# Sensors_Mic.net
KiCad netlist of a schematic drawn in Altium Designer
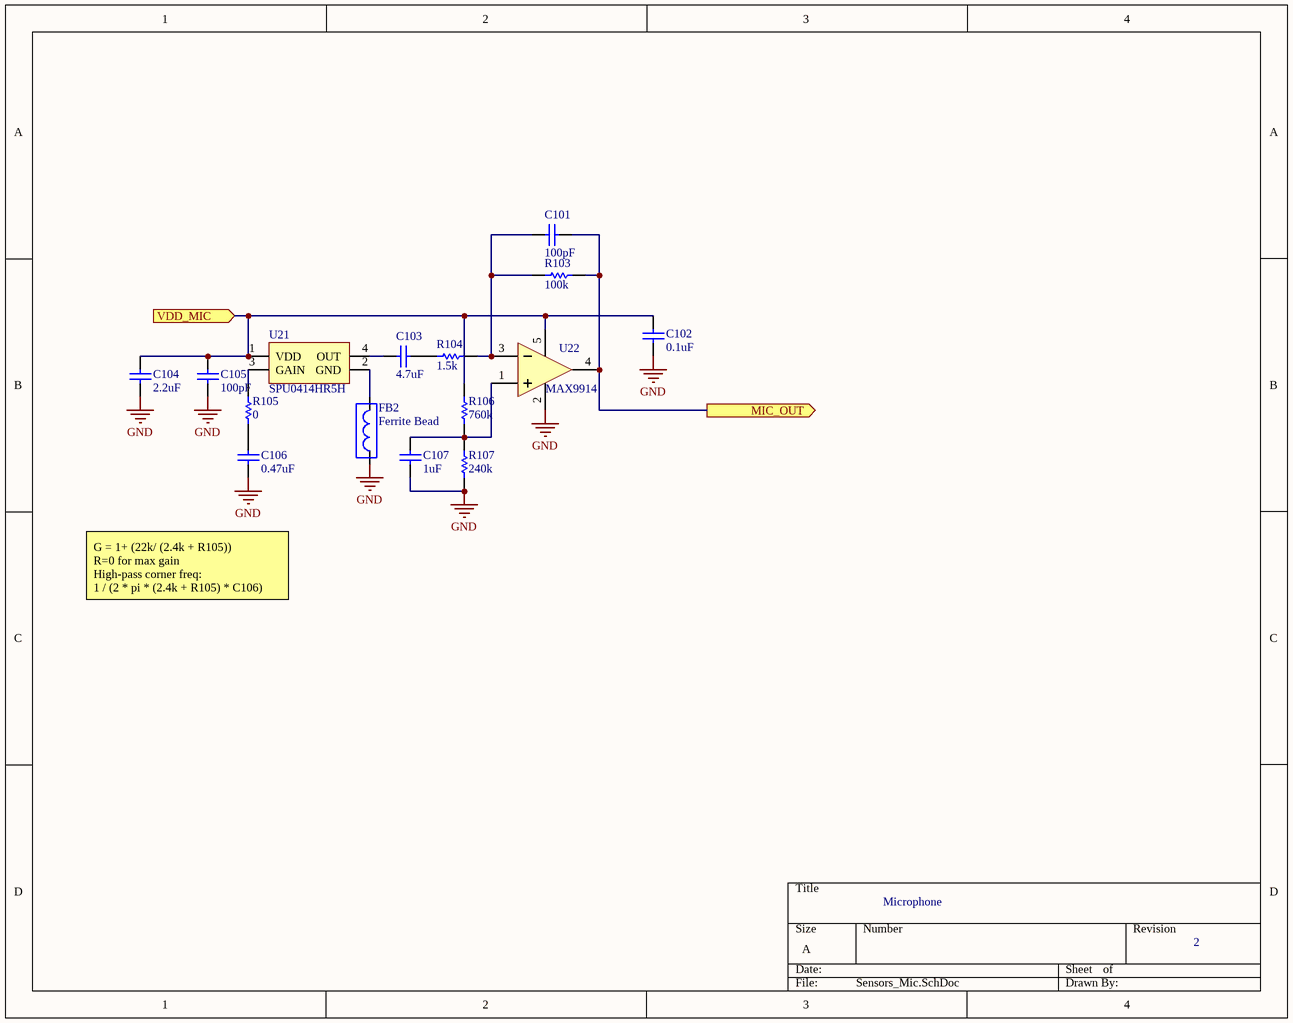
[diagram p0: Sensors_Mic.SchDoc]

(export (version "E")
  (design (tool "Eeschema 10.0.6"))
  (components
    (comp (ref "C101")
      (value "100pF")
      (footprint "0603")
      (description "Ceramic Capacitor (Surface Mount)")
      (fields
        (field (name "MANUFACTURER") "Kemet")
        (field (name "MANUFACTURER PART NUMBER") "C0603C101J5GACTU")
      )
      (libsource (lib "DRP_Basic_2014") (part "Cap"))
    )
    (comp (ref "C102")
      (value "0.1uF")
      (footprint "0603")
      (description "Ceramic Capacitor (Surface Mount)")
      (fields
        (field (name "MANUFACTURER") "Murata Electronics North America")
        (field (name "MANUFACTURER PART NUMBER") "GRM188R71C104KA01D")
      )
      (libsource (lib "DRP_Basic_2014") (part "Cap"))
    )
    (comp (ref "C103")
      (value "4.7uF")
      (footprint "0603")
      (description "Ceramic Capacitor (Surface Mount)")
      (fields
        (field (name "MANUFACTURER") "Samsung Electro-Mechanics")
        (field (name "MANUFACTURER PART NUMBER") "CL10B475KQ8NQNC")
      )
      (libsource (lib "DRP_Basic_2014") (part "Cap"))
    )
    (comp (ref "C104")
      (value "2.2uF")
      (footprint "0603")
      (description "Ceramic Capacitor (Surface Mount)")
      (fields
        (field (name "MANUFACTURER") "Murata Electronics North America")
        (field (name "MANUFACTURER PART NUMBER") "GRM188R61C225KE15D")
      )
      (libsource (lib "DRP_Basic_2014") (part "Cap"))
    )
    (comp (ref "C105")
      (value "100pF")
      (footprint "0603")
      (description "Ceramic Capacitor (Surface Mount)")
      (fields
        (field (name "MANUFACTURER") "Kemet")
        (field (name "MANUFACTURER PART NUMBER") "C0603C101J5GACTU")
      )
      (libsource (lib "DRP_Basic_2014") (part "Cap"))
    )
    (comp (ref "C106")
      (value "0.47uF")
      (footprint "0603")
      (description "Ceramic Capacitor (Surface Mount)")
      (fields
        (field (name "MANUFACTURER") "TDK Corporation")
        (field (name "MANUFACTURER PART NUMBER") "C1608X7R1C474K080AC")
      )
      (libsource (lib "DRP_Basic_2014") (part "Cap"))
    )
    (comp (ref "C107")
      (value "1uF")
      (footprint "0603")
      (description "Ceramic Capacitor (Surface Mount)")
      (fields
        (field (name "MANUFACTURER") "Murata Electronics North America")
        (field (name "MANUFACTURER PART NUMBER") "GRM188R61A105KA61D")
      )
      (libsource (lib "DRP_Basic_2014") (part "Cap"))
    )
    (comp (ref "FB2")
      (value "Ferrite Bead")
      (footprint "0603")
      (description "Ferrite bead, RF choke")
      (fields
        (field (name "DIGI-KEY PART NUMBER") "490-5216-1-ND")
        (field (name "MANUFACTURER") "Murata Electronics North America")
      )
      (libsource (lib "DRP_Basic_2014") (part "Ferrite Bead"))
    )
    (comp (ref "R103")
      (value "100k")
      (footprint "0603")
      (description "Chip Resistor (Surface Mount)")
      (fields
        (field (name "MANUFACTURER") "Yageo")
        (field (name "MANUFACTURER PART NUMBER") "RT0603FRE07100KL")
      )
      (libsource (lib "DRP_Basic_2014") (part "Res"))
    )
    (comp (ref "R104")
      (value "1.5k")
      (footprint "0603")
      (description "Chip Resistor (Surface Mount)")
      (fields
        (field (name "MANUFACTURER") "Vishay Dale")
        (field (name "MANUFACTURER PART NUMBER") "CRCW06031K50JNEA")
      )
      (libsource (lib "DRP_Basic_2014") (part "Res"))
    )
    (comp (ref "R105")
      (value "0")
      (footprint "0603")
      (description "Chip Resistor (Surface Mount)")
      (fields
        (field (name "MANUFACTURER") "Yageo")
        (field (name "MANUFACTURER PART NUMBER") "RC0603JR-070RL")
      )
      (libsource (lib "DRP_Basic_2014") (part "Res"))
    )
    (comp (ref "R106")
      (value "760k")
      (footprint "0603")
      (description "Chip Resistor (Surface Mount)")
      (fields
        (field (name "MANUFACTURER") "Yageo")
        (field (name "MANUFACTURER PART NUMBER") "RC0603FR-07750KL")
      )
      (libsource (lib "DRP_Basic_2014") (part "Res"))
    )
    (comp (ref "R107")
      (value "240k")
      (footprint "0603")
      (description "Chip Resistor (Surface Mount)")
      (fields
        (field (name "MANUFACTURER") "Yageo")
        (field (name "MANUFACTURER PART NUMBER") "RC0603FR-07240KL")
      )
      (libsource (lib "DRP_Basic_2014") (part "Res"))
    )
    (comp (ref "U21")
      (value "SPU0414HR5H")
      (footprint "SPU0414HR5H")
      (description "Knowles Analog Top MEMS Microphone")
      (fields
        (field (name "DIGI-KEY PART NUMBER") "423-1134-1-ND")
        (field (name "DISTRIBUTOR PART NUMBER") "721-SPU0414HR5H-SB")
      )
      (libsource (lib "Sprite") (part "SPU0414HR5H"))
    )
    (comp (ref "U22")
      (value "MAX9914")
      (footprint "SC70-5")
      (description "Low power opamp")
      (fields
        (field (name "DIGI-KEY PART NUMBER") "MAX9914EXK+TCT-ND")
        (field (name "DISTRIBUTOR PART NUMBER") "700-MAX9914EXKT")
      )
      (libsource (lib "DRP_Basic_2014") (part "OPA333, 2333"))
    )
  )
  (nets
    (net (code "1") (name "/MIC_OUT") (class "Default")
      (node (ref "C101") (pin "2") (pinfunction "2_2") (pintype "passive"))
      (node (ref "R103") (pin "2") (pinfunction "2_2") (pintype "passive"))
      (node (ref "U22") (pin "4") (pinfunction "TAB_4") (pintype "passive"))
    )
    (net (code "2") (name "/VDD_MIC") (class "Default")
      (node (ref "C102") (pin "2") (pinfunction "2_2") (pintype "passive"))
      (node (ref "C104") (pin "2") (pinfunction "2_2") (pintype "passive"))
      (node (ref "C105") (pin "2") (pinfunction "2_2") (pintype "passive"))
      (node (ref "R106") (pin "2") (pinfunction "2_2") (pintype "passive"))
      (node (ref "U21") (pin "1") (pinfunction "VDD_1") (pintype "power_in"))
      (node (ref "U22") (pin "5") (pinfunction "OS_NUL_5") (pintype "passive"))
    )
    (net (code "3") (name "GND") (class "Default")
      (node (ref "C102") (pin "1") (pinfunction "1_1") (pintype "passive"))
      (node (ref "C104") (pin "1") (pinfunction "1_1") (pintype "passive"))
      (node (ref "C105") (pin "1") (pinfunction "1_1") (pintype "passive"))
      (node (ref "C106") (pin "1") (pinfunction "1_1") (pintype "passive"))
      (node (ref "C107") (pin "1") (pinfunction "1_1") (pintype "passive"))
      (node (ref "FB2") (pin "1") (pinfunction "1_1") (pintype "passive"))
      (node (ref "R107") (pin "1") (pinfunction "1_1") (pintype "passive"))
      (node (ref "U22") (pin "2") (pinfunction "IN-_2") (pintype "passive"))
    )
    (net (code "4") (name "Net-(C103-Pad2)") (class "Default")
      (node (ref "C103") (pin "2") (pinfunction "2_2") (pintype "passive"))
      (node (ref "R104") (pin "1") (pinfunction "1_1") (pintype "passive"))
    )
    (net (code "5") (name "Net-(C106-Pad2)") (class "Default")
      (node (ref "C106") (pin "2") (pinfunction "2_2") (pintype "passive"))
      (node (ref "R105") (pin "1") (pinfunction "1_1") (pintype "passive"))
    )
    (net (code "6") (name "Net-(C107-Pad2)") (class "Default")
      (node (ref "C107") (pin "2") (pinfunction "2_2") (pintype "passive"))
      (node (ref "R106") (pin "1") (pinfunction "1_1") (pintype "passive"))
      (node (ref "R107") (pin "2") (pinfunction "2_2") (pintype "passive"))
      (node (ref "U22") (pin "1") (pinfunction "OS_NUL_1") (pintype "passive"))
    )
    (net (code "7") (name "Net-(U21-GAIN)") (class "Default")
      (node (ref "R105") (pin "2") (pinfunction "2_2") (pintype "passive"))
      (node (ref "U21") (pin "3") (pinfunction "GAIN_3") (pintype "passive"))
    )
    (net (code "8") (name "Net-(U21-GND)") (class "Default")
      (node (ref "FB2") (pin "2") (pinfunction "2_2") (pintype "passive"))
      (node (ref "U21") (pin "2") (pinfunction "GND_2") (pintype "power_in"))
    )
    (net (code "9") (name "Net-(U21-OUT)") (class "Default")
      (node (ref "C103") (pin "1") (pinfunction "1_1") (pintype "passive"))
      (node (ref "U21") (pin "4") (pinfunction "OUT_4") (pintype "power_in"))
    )
    (net (code "10") (name "Net-(U22-IN+)") (class "Default")
      (node (ref "C101") (pin "1") (pinfunction "1_1") (pintype "passive"))
      (node (ref "R103") (pin "1") (pinfunction "1_1") (pintype "passive"))
      (node (ref "R104") (pin "2") (pinfunction "2_2") (pintype "passive"))
      (node (ref "U22") (pin "3") (pinfunction "IN+_3") (pintype "passive"))
    )
  )
)
